# A111_Pulsed_Radar_Breakout.net
KiCad netlist of a schematic drawn in EAGLE
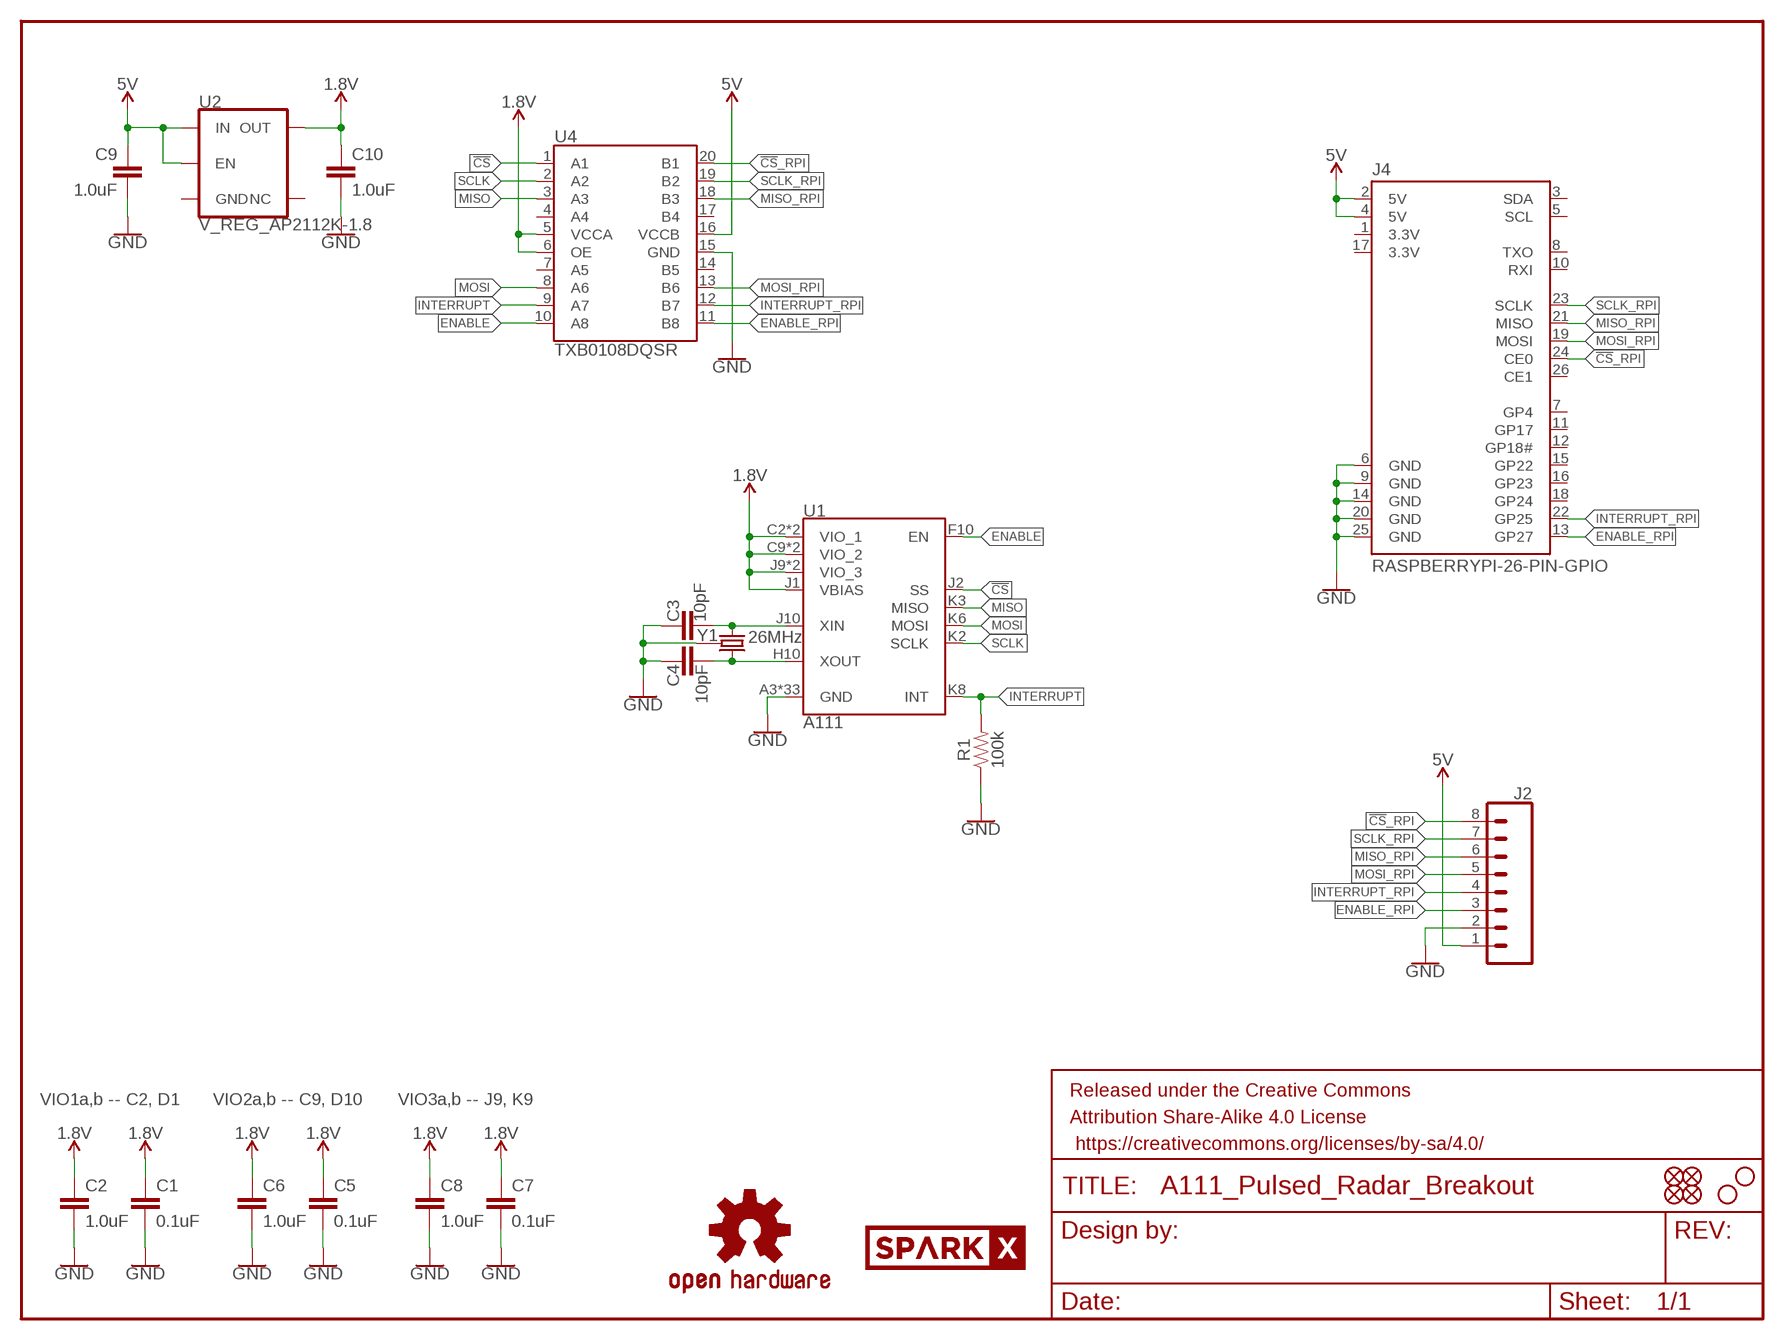
[diagram p0: schematic, sheet 1]

(export (version "E")
  (design (tool "Eeschema 10.0.6"))
  (components
    (comp (ref "C1")
      (value "0.1uF")
      (footprint "eagle-import:0603")
      (libsource (lib "eagle-import") (part "0.1UF-0603-25V-(+80/-20%)"))
    )
    (comp (ref "C2")
      (value "1.0uF")
      (footprint "eagle-import:0603")
      (libsource (lib "eagle-import") (part "1.0UF-0603-16V-10%"))
    )
    (comp (ref "C3")
      (value "10pF")
      (footprint "eagle-import:0603")
      (libsource (lib "eagle-import") (part "10PF-0603-50V-5%"))
    )
    (comp (ref "C4")
      (value "10pF")
      (footprint "eagle-import:0603")
      (libsource (lib "eagle-import") (part "10PF-0603-50V-5%"))
    )
    (comp (ref "C5")
      (value "0.1uF")
      (footprint "eagle-import:0603")
      (libsource (lib "eagle-import") (part "0.1UF-0603-25V-(+80/-20%)"))
    )
    (comp (ref "C6")
      (value "1.0uF")
      (footprint "eagle-import:0603")
      (libsource (lib "eagle-import") (part "1.0UF-0603-16V-10%"))
    )
    (comp (ref "C7")
      (value "0.1uF")
      (footprint "eagle-import:0603")
      (libsource (lib "eagle-import") (part "0.1UF-0603-25V-(+80/-20%)"))
    )
    (comp (ref "C8")
      (value "1.0uF")
      (footprint "eagle-import:0603")
      (libsource (lib "eagle-import") (part "1.0UF-0603-16V-10%"))
    )
    (comp (ref "C9")
      (value "1.0uF")
      (footprint "eagle-import:0603")
      (libsource (lib "eagle-import") (part "1.0UF-0603-16V-10%"))
    )
    (comp (ref "C10")
      (value "1.0uF")
      (footprint "eagle-import:0603")
      (libsource (lib "eagle-import") (part "1.0UF-0603-16V-10%"))
    )
    (comp (ref "FD1")
      (value "FIDUCIALUFIDUCIAL")
      (footprint "eagle-import:FIDUCIAL-MICRO")
      (libsource (lib "eagle-import") (part "FIDUCIALUFIDUCIAL"))
    )
    (comp (ref "FD2")
      (value "FIDUCIALUFIDUCIAL")
      (footprint "eagle-import:FIDUCIAL-MICRO")
      (libsource (lib "eagle-import") (part "FIDUCIALUFIDUCIAL"))
    )
    (comp (ref "FD3")
      (value "FIDUCIALUFIDUCIAL")
      (footprint "eagle-import:FIDUCIAL-MICRO")
      (libsource (lib "eagle-import") (part "FIDUCIALUFIDUCIAL"))
    )
    (comp (ref "FD4")
      (value "FIDUCIALUFIDUCIAL")
      (footprint "eagle-import:FIDUCIAL-MICRO")
      (libsource (lib "eagle-import") (part "FIDUCIALUFIDUCIAL"))
    )
    (comp (ref "FRAME1")
      (value "FRAME-LETTER")
      (footprint "eagle-import:CREATIVE_COMMONS")
      (libsource (lib "eagle-import") (part "FRAME-LETTER"))
    )
    (comp (ref "H1")
      (value "STAND-OFF")
      (footprint "eagle-import:STAND-OFF")
      (libsource (lib "eagle-import") (part "STAND-OFF"))
    )
    (comp (ref "H2")
      (value "STAND-OFF")
      (footprint "eagle-import:STAND-OFF")
      (libsource (lib "eagle-import") (part "STAND-OFF"))
    )
    (comp (ref "J2")
      (value "CONN_08NO_SILK_FEMALE_PTH")
      (footprint "eagle-import:1X08_NO_SILK")
      (libsource (lib "eagle-import") (part "CONN_08NO_SILK_FEMALE_PTH"))
    )
    (comp (ref "J4")
      (value "RASPBERRYPI-26-PIN-GPIO")
      (footprint "eagle-import:2X13")
      (libsource (lib "eagle-import") (part "RASPBERRYPI-26-PIN-GPIO"))
    )
    (comp (ref "LOGO1")
      (value "SPARKX-LOGO5")
      (footprint "eagle-import:SPARKX-LARGE")
      (libsource (lib "eagle-import") (part "SPARKX-LOGO5"))
    )
    (comp (ref "LOGO2")
      (value "OSHW-LOGOM")
      (footprint "eagle-import:OSHW-LOGO-M")
      (libsource (lib "eagle-import") (part "OSHW-LOGOM"))
    )
    (comp (ref "R1")
      (value "100k")
      (footprint "eagle-import:0603")
      (libsource (lib "eagle-import") (part "100KOHM-0603-1/10W-1%"))
    )
    (comp (ref "U1")
      (value "A111")
      (footprint "eagle-import:A111")
      (libsource (lib "eagle-import") (part "A111"))
    )
    (comp (ref "U2")
      (value "V_REG_AP2112K-1.8")
      (footprint "eagle-import:SOT23-5")
      (libsource (lib "eagle-import") (part "V_REG_AP2112K-1.8"))
    )
    (comp (ref "U4")
      (value "TXB0108DQSR")
      (footprint "eagle-import:UFDFN-20")
      (libsource (lib "eagle-import") (part "TXB0108"))
    )
    (comp (ref "Y1")
      (value "26MHz")
      (footprint "eagle-import:CRYSTAL-SMD-3.2X2.5MM")
      (libsource (lib "eagle-import") (part "CRYSTAL-26MHZSMD-3.2X2.5"))
    )
  )
  (nets
    (net (code "1") (name "/~{CS}") (class "Default")
      (node (ref "U1") (pin "J2") (pinfunction "SS_J2") (pintype "bidirectional"))
      (node (ref "U4") (pin "1") (pinfunction "A1_1") (pintype "bidirectional"))
    )
    (net (code "2") (name "/~{CS}_RPI") (class "Default")
      (node (ref "J2") (pin "8") (pinfunction "8_8") (pintype "passive"))
      (node (ref "J4") (pin "24") (pinfunction "CE0_24") (pintype "output"))
      (node (ref "U4") (pin "20") (pinfunction "B1_20") (pintype "bidirectional"))
    )
    (net (code "3") (name "1.8V") (class "Default")
      (node (ref "C1") (pin "1") (pinfunction "1_1") (pintype "passive"))
      (node (ref "C10") (pin "1") (pinfunction "1_1") (pintype "passive"))
      (node (ref "C2") (pin "1") (pinfunction "1_1") (pintype "passive"))
      (node (ref "C5") (pin "1") (pinfunction "1_1") (pintype "passive"))
      (node (ref "C6") (pin "1") (pinfunction "1_1") (pintype "passive"))
      (node (ref "C7") (pin "1") (pinfunction "1_1") (pintype "passive"))
      (node (ref "C8") (pin "1") (pinfunction "1_1") (pintype "passive"))
      (node (ref "U1") (pin "C2") (pinfunction "VIO_1_C2") (pintype "bidirectional"))
      (node (ref "U1") (pin "C9") (pinfunction "VIO_2_C9") (pintype "bidirectional"))
      (node (ref "U1") (pin "D1") (pinfunction "VIO_1_D1") (pintype "bidirectional"))
      (node (ref "U1") (pin "D10") (pinfunction "VIO_2_D10") (pintype "bidirectional"))
      (node (ref "U1") (pin "J1") (pinfunction "VBIAS_J1") (pintype "bidirectional"))
      (node (ref "U1") (pin "J9") (pinfunction "VIO_3_J9") (pintype "bidirectional"))
      (node (ref "U1") (pin "K9") (pinfunction "VIO_3_K9") (pintype "bidirectional"))
      (node (ref "U2") (pin "5") (pinfunction "OUT_5") (pintype "passive"))
      (node (ref "U4") (pin "5") (pinfunction "VCCA_5") (pintype "bidirectional"))
      (node (ref "U4") (pin "6") (pinfunction "OE_6") (pintype "bidirectional"))
    )
    (net (code "4") (name "5V") (class "Default")
      (node (ref "C9") (pin "1") (pinfunction "1_1") (pintype "passive"))
      (node (ref "J2") (pin "1") (pinfunction "1_1") (pintype "passive"))
      (node (ref "J4") (pin "2") (pinfunction "5V_2") (pintype "power_in"))
      (node (ref "J4") (pin "4") (pinfunction "5V_4") (pintype "power_in"))
      (node (ref "U2") (pin "1") (pinfunction "IN_1") (pintype "input"))
      (node (ref "U2") (pin "3") (pinfunction "EN_3") (pintype "input"))
      (node (ref "U4") (pin "16") (pinfunction "VCCB_16") (pintype "bidirectional"))
    )
    (net (code "5") (name "ENABLE") (class "Default")
      (node (ref "U1") (pin "F10") (pinfunction "EN_F10") (pintype "bidirectional"))
      (node (ref "U4") (pin "10") (pinfunction "A8_10") (pintype "bidirectional"))
    )
    (net (code "6") (name "ENABLE_RPI") (class "Default")
      (node (ref "J2") (pin "3") (pinfunction "3_3") (pintype "passive"))
      (node (ref "J4") (pin "13") (pinfunction "GP27_13") (pintype "bidirectional"))
      (node (ref "U4") (pin "11") (pinfunction "B8_11") (pintype "bidirectional"))
    )
    (net (code "7") (name "GND") (class "Default")
      (node (ref "C1") (pin "2") (pinfunction "2_2") (pintype "passive"))
      (node (ref "C10") (pin "2") (pinfunction "2_2") (pintype "passive"))
      (node (ref "C2") (pin "2") (pinfunction "2_2") (pintype "passive"))
      (node (ref "C3") (pin "2") (pinfunction "2_2") (pintype "passive"))
      (node (ref "C4") (pin "1") (pinfunction "1_1") (pintype "passive"))
      (node (ref "C5") (pin "2") (pinfunction "2_2") (pintype "passive"))
      (node (ref "C6") (pin "2") (pinfunction "2_2") (pintype "passive"))
      (node (ref "C7") (pin "2") (pinfunction "2_2") (pintype "passive"))
      (node (ref "C8") (pin "2") (pinfunction "2_2") (pintype "passive"))
      (node (ref "C9") (pin "2") (pinfunction "2_2") (pintype "passive"))
      (node (ref "J2") (pin "2") (pinfunction "2_2") (pintype "passive"))
      (node (ref "J4") (pin "14") (pinfunction "GND_14") (pintype "power_in"))
      (node (ref "J4") (pin "20") (pinfunction "GND_20") (pintype "power_in"))
      (node (ref "J4") (pin "25") (pinfunction "GND_25") (pintype "power_in"))
      (node (ref "J4") (pin "6") (pinfunction "GND_6") (pintype "power_in"))
      (node (ref "J4") (pin "9") (pinfunction "GND_9") (pintype "power_in"))
      (node (ref "R1") (pin "1") (pinfunction "1_1") (pintype "passive"))
      (node (ref "U1") (pin "A3") (pinfunction "GND_A3") (pintype "bidirectional"))
      (node (ref "U1") (pin "A4") (pinfunction "GND_A4") (pintype "bidirectional"))
      (node (ref "U1") (pin "A5") (pinfunction "GND_A5") (pintype "bidirectional"))
      (node (ref "U1") (pin "A6") (pinfunction "GND_A6") (pintype "bidirectional"))
      (node (ref "U1") (pin "A7") (pinfunction "GND_A7") (pintype "bidirectional"))
      (node (ref "U1") (pin "A8") (pinfunction "GND_A8") (pintype "bidirectional"))
      (node (ref "U1") (pin "A9") (pinfunction "GND_A9") (pintype "bidirectional"))
      (node (ref "U1") (pin "B10") (pinfunction "GND_B10") (pintype "bidirectional"))
      (node (ref "U1") (pin "B2") (pinfunction "GND_B2") (pintype "bidirectional"))
      (node (ref "U1") (pin "B9") (pinfunction "GND_B9") (pintype "bidirectional"))
      (node (ref "U1") (pin "C1") (pinfunction "GND_C1") (pintype "bidirectional"))
      (node (ref "U1") (pin "C10") (pinfunction "GND_C10") (pintype "bidirectional"))
      (node (ref "U1") (pin "D2") (pinfunction "GND_D2") (pintype "bidirectional"))
      (node (ref "U1") (pin "D9") (pinfunction "GND_D9") (pintype "bidirectional"))
      (node (ref "U1") (pin "E1") (pinfunction "GND_E1") (pintype "bidirectional"))
      (node (ref "U1") (pin "E10") (pinfunction "GND_E10") (pintype "bidirectional"))
      (node (ref "U1") (pin "E2") (pinfunction "GND_E2") (pintype "bidirectional"))
      (node (ref "U1") (pin "E9") (pinfunction "GND_E9") (pintype "bidirectional"))
      (node (ref "U1") (pin "F1") (pinfunction "GND_F1") (pintype "bidirectional"))
      (node (ref "U1") (pin "F2") (pinfunction "GND_F2") (pintype "bidirectional"))
      (node (ref "U1") (pin "F9") (pinfunction "GND_F9") (pintype "bidirectional"))
      (node (ref "U1") (pin "G1") (pinfunction "GND_G1") (pintype "bidirectional"))
      (node (ref "U1") (pin "G10") (pinfunction "GND_G10") (pintype "bidirectional"))
      (node (ref "U1") (pin "H1") (pinfunction "GND_H1") (pintype "bidirectional"))
      (node (ref "U1") (pin "H2") (pinfunction "GND_H2") (pintype "bidirectional"))
      (node (ref "U1") (pin "H9") (pinfunction "GND_H9") (pintype "bidirectional"))
      (node (ref "U1") (pin "J3") (pinfunction "GND_J3") (pintype "bidirectional"))
      (node (ref "U1") (pin "J5") (pinfunction "GND_J5") (pintype "bidirectional"))
      (node (ref "U1") (pin "J6") (pinfunction "GND_J6") (pintype "bidirectional"))
      (node (ref "U1") (pin "J8") (pinfunction "GND_J8") (pintype "bidirectional"))
      (node (ref "U1") (pin "K4") (pinfunction "GND_K4") (pintype "bidirectional"))
      (node (ref "U1") (pin "K5") (pinfunction "GND_K5") (pintype "bidirectional"))
      (node (ref "U1") (pin "K7") (pinfunction "GND_K7") (pintype "bidirectional"))
      (node (ref "U4") (pin "15") (pinfunction "GND_15") (pintype "bidirectional"))
      (node (ref "Y1") (pin "2") (pinfunction "3_2") (pintype "passive"))
      (node (ref "Y1") (pin "4") (pinfunction "3_4") (pintype "passive"))
    )
    (net (code "8") (name "INTERRUPT") (class "Default")
      (node (ref "R1") (pin "2") (pinfunction "2_2") (pintype "passive"))
      (node (ref "U1") (pin "K8") (pinfunction "INT_K8") (pintype "bidirectional"))
      (node (ref "U4") (pin "9") (pinfunction "A7_9") (pintype "bidirectional"))
    )
    (net (code "9") (name "INTERRUPT_RPI") (class "Default")
      (node (ref "J2") (pin "4") (pinfunction "4_4") (pintype "passive"))
      (node (ref "J4") (pin "22") (pinfunction "GP25_22") (pintype "bidirectional"))
      (node (ref "U4") (pin "12") (pinfunction "B7_12") (pintype "bidirectional"))
    )
    (net (code "10") (name "MISO") (class "Default")
      (node (ref "U1") (pin "K3") (pinfunction "MISO_K3") (pintype "bidirectional"))
      (node (ref "U4") (pin "3") (pinfunction "A3_3") (pintype "bidirectional"))
    )
    (net (code "11") (name "MISO_RPI") (class "Default")
      (node (ref "J2") (pin "6") (pinfunction "6_6") (pintype "passive"))
      (node (ref "J4") (pin "21") (pinfunction "MISO_21") (pintype "input"))
      (node (ref "U4") (pin "18") (pinfunction "B3_18") (pintype "bidirectional"))
    )
    (net (code "12") (name "MOSI") (class "Default")
      (node (ref "U1") (pin "K6") (pinfunction "MOSI_K6") (pintype "bidirectional"))
      (node (ref "U4") (pin "8") (pinfunction "A6_8") (pintype "bidirectional"))
    )
    (net (code "13") (name "MOSI_RPI") (class "Default")
      (node (ref "J2") (pin "5") (pinfunction "5_5") (pintype "passive"))
      (node (ref "J4") (pin "19") (pinfunction "MOSI_19") (pintype "output"))
      (node (ref "U4") (pin "13") (pinfunction "B6_13") (pintype "bidirectional"))
    )
    (net (code "14") (name "Net-(U1-XIN)") (class "Default")
      (node (ref "C3") (pin "1") (pinfunction "1_1") (pintype "passive"))
      (node (ref "U1") (pin "J10") (pinfunction "XIN_J10") (pintype "bidirectional"))
      (node (ref "Y1") (pin "1") (pinfunction "1_1") (pintype "passive"))
    )
    (net (code "15") (name "Net-(U1-XOUT)") (class "Default")
      (node (ref "C4") (pin "2") (pinfunction "2_2") (pintype "passive"))
      (node (ref "U1") (pin "H10") (pinfunction "XOUT_H10") (pintype "bidirectional"))
      (node (ref "Y1") (pin "3") (pinfunction "2_3") (pintype "passive"))
    )
    (net (code "16") (name "SCLK") (class "Default")
      (node (ref "U1") (pin "K2") (pinfunction "SCLK_K2") (pintype "bidirectional"))
      (node (ref "U4") (pin "2") (pinfunction "A2_2") (pintype "bidirectional"))
    )
    (net (code "17") (name "SCLK_RPI") (class "Default")
      (node (ref "J2") (pin "7") (pinfunction "7_7") (pintype "passive"))
      (node (ref "J4") (pin "23") (pinfunction "SCLK_23") (pintype "output"))
      (node (ref "U4") (pin "19") (pinfunction "B2_19") (pintype "bidirectional"))
    )
    (net (code "18") (name "unconnected-(J4-3.3V-Pad1)") (class "Default")
      (node (ref "J4") (pin "1") (pinfunction "3.3V_1") (pintype "no_connect"))
    )
    (net (code "19") (name "unconnected-(J4-3.3V-Pad17)") (class "Default")
      (node (ref "J4") (pin "17") (pinfunction "3.3V_17") (pintype "no_connect"))
    )
    (net (code "20") (name "unconnected-(J4-CE1-Pad26)") (class "Default")
      (node (ref "J4") (pin "26") (pinfunction "CE1_26") (pintype "output"))
    )
    (net (code "21") (name "unconnected-(J4-GP4-Pad7)") (class "Default")
      (node (ref "J4") (pin "7") (pinfunction "GP4_7") (pintype "bidirectional"))
    )
    (net (code "22") (name "unconnected-(J4-GP17-Pad11)") (class "Default")
      (node (ref "J4") (pin "11") (pinfunction "GP17_11") (pintype "bidirectional"))
    )
    (net (code "23") (name "unconnected-(J4-GP18#-Pad12)") (class "Default")
      (node (ref "J4") (pin "12") (pinfunction "GP18#_12") (pintype "bidirectional"))
    )
    (net (code "24") (name "unconnected-(J4-GP22-Pad15)") (class "Default")
      (node (ref "J4") (pin "15") (pinfunction "GP22_15") (pintype "bidirectional"))
    )
    (net (code "25") (name "unconnected-(J4-GP23-Pad16)") (class "Default")
      (node (ref "J4") (pin "16") (pinfunction "GP23_16") (pintype "bidirectional"))
    )
    (net (code "26") (name "unconnected-(J4-GP24-Pad18)") (class "Default")
      (node (ref "J4") (pin "18") (pinfunction "GP24_18") (pintype "bidirectional"))
    )
    (net (code "27") (name "unconnected-(J4-RXI-Pad10)") (class "Default")
      (node (ref "J4") (pin "10") (pinfunction "RXI_10") (pintype "input"))
    )
    (net (code "28") (name "unconnected-(J4-SCL-Pad5)") (class "Default")
      (node (ref "J4") (pin "5") (pinfunction "SCL_5") (pintype "bidirectional"))
    )
    (net (code "29") (name "unconnected-(J4-SDA-Pad3)") (class "Default")
      (node (ref "J4") (pin "3") (pinfunction "SDA_3") (pintype "bidirectional"))
    )
    (net (code "30") (name "unconnected-(J4-TXO-Pad8)") (class "Default")
      (node (ref "J4") (pin "8") (pinfunction "TXO_8") (pintype "output"))
    )
    (net (code "31") (name "unconnected-(U2-GND-Pad2)") (class "Default")
      (node (ref "U2") (pin "2") (pinfunction "GND_2") (pintype "input"))
    )
    (net (code "32") (name "unconnected-(U2-NC-Pad4)") (class "Default")
      (node (ref "U2") (pin "4") (pinfunction "NC_4") (pintype "no_connect"))
    )
    (net (code "33") (name "unconnected-(U4-A4-Pad4)") (class "Default")
      (node (ref "U4") (pin "4") (pinfunction "A4_4") (pintype "bidirectional"))
    )
    (net (code "34") (name "unconnected-(U4-A5-Pad7)") (class "Default")
      (node (ref "U4") (pin "7") (pinfunction "A5_7") (pintype "bidirectional"))
    )
    (net (code "35") (name "unconnected-(U4-B4-Pad17)") (class "Default")
      (node (ref "U4") (pin "17") (pinfunction "B4_17") (pintype "bidirectional"))
    )
    (net (code "36") (name "unconnected-(U4-B5-Pad14)") (class "Default")
      (node (ref "U4") (pin "14") (pinfunction "B5_14") (pintype "bidirectional"))
    )
  )
)
